# DAC_Filter.net
KiCad netlist of a schematic drawn in Altium Designer
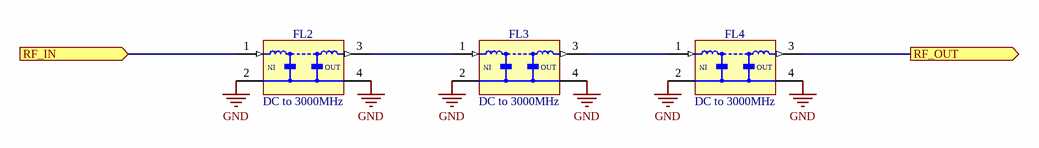
[diagram p0: DAC_Filter.SchDoc]

(export (version "E")
  (design (tool "Eeschema 10.0.6"))
  (components
    (comp (ref "FL2")
      (value "DC to 3000MHz")
      (footprint "FIL_MINI-CIRCUITS_FV1206")
      (description "50 Ohm DC to 3000MHz Low Pass Filter")
      (fields
        (field (name "PART NUMBER") "FIL_MINI-CIRCUITS_LFCN-3000+")
        (field (name "MANUFACTURER") "MINI-CIRCUITS")
        (field (name "AUTHOR") "CERN DEM JLC")
      )
      (libsource (lib "Inductors & Transformers") (part "FIL_MINI-CIRCUITS_LFCN-3000+"))
    )
    (comp (ref "FL3")
      (value "DC to 3000MHz")
      (footprint "FIL_MINI-CIRCUITS_FV1206")
      (description "50 Ohm DC to 3000MHz Low Pass Filter")
      (fields
        (field (name "PART NUMBER") "FIL_MINI-CIRCUITS_LFCN-3000+")
        (field (name "MANUFACTURER") "MINI-CIRCUITS")
        (field (name "AUTHOR") "CERN DEM JLC")
      )
      (libsource (lib "Inductors & Transformers") (part "FIL_MINI-CIRCUITS_LFCN-3000+"))
    )
    (comp (ref "FL4")
      (value "DC to 3000MHz")
      (footprint "FIL_MINI-CIRCUITS_FV1206")
      (description "50 Ohm DC to 3000MHz Low Pass Filter")
      (fields
        (field (name "PART NUMBER") "FIL_MINI-CIRCUITS_LFCN-3000+")
        (field (name "MANUFACTURER") "MINI-CIRCUITS")
        (field (name "AUTHOR") "CERN DEM JLC")
      )
      (libsource (lib "Inductors & Transformers") (part "FIL_MINI-CIRCUITS_LFCN-3000+"))
    )
  )
  (nets
    (net (code "1") (name "/RF_IN") (class "Default")
      (node (ref "FL2") (pin "1") (pinfunction "RFIN_1") (pintype "input"))
    )
    (net (code "2") (name "/RF_OUT") (class "Default")
      (node (ref "FL4") (pin "3") (pinfunction "RFOUT_3") (pintype "output"))
    )
    (net (code "3") (name "GND") (class "Default")
      (node (ref "FL2") (pin "2") (pinfunction "GND_2") (pintype "power_in"))
      (node (ref "FL2") (pin "4") (pinfunction "GND_4") (pintype "power_in"))
      (node (ref "FL3") (pin "2") (pinfunction "GND_2") (pintype "power_in"))
      (node (ref "FL3") (pin "4") (pinfunction "GND_4") (pintype "power_in"))
      (node (ref "FL4") (pin "2") (pinfunction "GND_2") (pintype "power_in"))
      (node (ref "FL4") (pin "4") (pinfunction "GND_4") (pintype "power_in"))
    )
    (net (code "4") (name "Net-(FL2-RFOUT)") (class "Default")
      (node (ref "FL2") (pin "3") (pinfunction "RFOUT_3") (pintype "output"))
      (node (ref "FL3") (pin "1") (pinfunction "RFIN_1") (pintype "input"))
    )
    (net (code "5") (name "Net-(FL3-RFOUT)") (class "Default")
      (node (ref "FL3") (pin "3") (pinfunction "RFOUT_3") (pintype "output"))
      (node (ref "FL4") (pin "1") (pinfunction "RFIN_1") (pintype "input"))
    )
  )
)
